# Logic_Power.net
KiCad netlist of a schematic drawn in Altium Designer
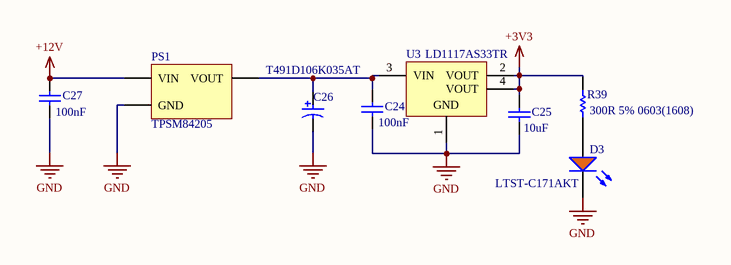
[diagram p0: Logic_Power.SchDoc]

(export (version "E")
  (design (tool "Eeschema 10.0.6"))
  (components
    (comp (ref "C24")
      (value "100nF")
      (footprint "CAPC0805(2012)145_L")
      (description "0805 (2012 Metric) Chip Capacitor")
      (libsource (lib "Altium Content Vault") (part "CAP_5"))
    )
    (comp (ref "C25")
      (value "10uF")
      (footprint "CAPC0805(2012)145_L")
      (description "0805 (2012 Metric) Chip Capacitor")
      (libsource (lib "Altium Content Vault") (part "CAP_5"))
    )
    (comp (ref "C26")
      (value "T491D106K035AT")
      (footprint "KEMT-T491-D_L")
      (description "Tantalum Capacitor, 10 uF, +/- 10%, 35 V, -55 to 125 degC, 2-Pin SMD, RoHS, Tape and Reel")
      (fields (field (name "MANUFACTURER") "Kemet") (field (name "TOLERANCE") "20%"))
      (libsource (lib "Altium Content Vault") (part "CAP-P-2"))
    )
    (comp (ref "C27")
      (value "100nF")
      (footprint "CAPC0805(2012)145_L")
      (description "0805 (2012 Metric) Chip Capacitor")
      (libsource (lib "Altium Content Vault") (part "CAP_5"))
    )
    (comp (ref "D3")
      (value "LTST-C171AKT")
      (footprint "LTST-C171AKT_V")
      (description "LED AMBER CLR THIN 0805 SMD")
      (fields (field (name "MANUFACTURER") "Lite-On"))
      (libsource (lib "Altium Content Vault") (part "LED_AMBER_AC"))
    )
    (comp (ref "PS1")
      (value "TPSM84205")
      (footprint "tpsm84205")
      (libsource (lib "SE_Lib") (part "tpsm84205"))
    )
    (comp (ref "R39")
      (value "300R 5% 0603(1608)")
      (footprint "RESC0603(1608)_N")
      (description "100K 0.1W 5% 0603 (1608 Metric)  SMD")
      (fields (field (name "TOLERANCE") "5 %") (field (name "POWER") "0.1 W"))
      (libsource (lib "Altium Content Vault") (part "RES"))
    )
    (comp (ref "U3")
      (value "LD1117AS33TR")
      (footprint "SOT-223_M")
      (description "1A, Low Drop Positive Voltage Regulator, 3.3V, 4-Pin SOT-223, Tape and Reel")
      (libsource (lib "Altium Content Vault") (part "PM-REG-LD1117-SOT4"))
    )
  )
  (nets
    (net (code "1") (name "+3V3") (class "Default")
      (node (ref "C25") (pin "2") (pinfunction "2_2") (pintype "passive"))
      (node (ref "R39") (pin "2") (pinfunction "2_2") (pintype "passive"))
      (node (ref "U3") (pin "2") (pinfunction "VOUT_2") (pintype "power_in"))
      (node (ref "U3") (pin "4") (pinfunction "VOUT_4") (pintype "power_in"))
    )
    (net (code "2") (name "+12V") (class "Default")
      (node (ref "C27") (pin "2") (pinfunction "2_2") (pintype "passive"))
      (node (ref "PS1") (pin "1") (pinfunction "VIN_1") (pintype "passive"))
    )
    (net (code "3") (name "GND") (class "Default")
      (node (ref "C24") (pin "1") (pinfunction "1_1") (pintype "passive"))
      (node (ref "C25") (pin "1") (pinfunction "1_1") (pintype "passive"))
      (node (ref "C26") (pin "2") (pinfunction "2_2") (pintype "passive"))
      (node (ref "C27") (pin "1") (pinfunction "1_1") (pintype "passive"))
      (node (ref "D3") (pin "C") (pinfunction "C_C") (pintype "passive"))
      (node (ref "PS1") (pin "2") (pinfunction "GND_2") (pintype "passive"))
      (node (ref "U3") (pin "1") (pinfunction "GND_1") (pintype "power_in"))
    )
    (net (code "4") (name "Net-(D3-PadA)") (class "Default")
      (node (ref "D3") (pin "A") (pinfunction "A_A") (pintype "passive"))
      (node (ref "R39") (pin "1") (pinfunction "1_1") (pintype "passive"))
    )
    (net (code "5") (name "Net-(PS1-VOUT)") (class "Default")
      (node (ref "C24") (pin "2") (pinfunction "2_2") (pintype "passive"))
      (node (ref "C26") (pin "1") (pinfunction "1_1") (pintype "passive"))
      (node (ref "PS1") (pin "3") (pinfunction "VOUT_3") (pintype "passive"))
      (node (ref "U3") (pin "3") (pinfunction "VIN_3") (pintype "power_in"))
    )
  )
)
